# JW24A10L_revB.net
KiCad netlist of a schematic drawn in EAGLE
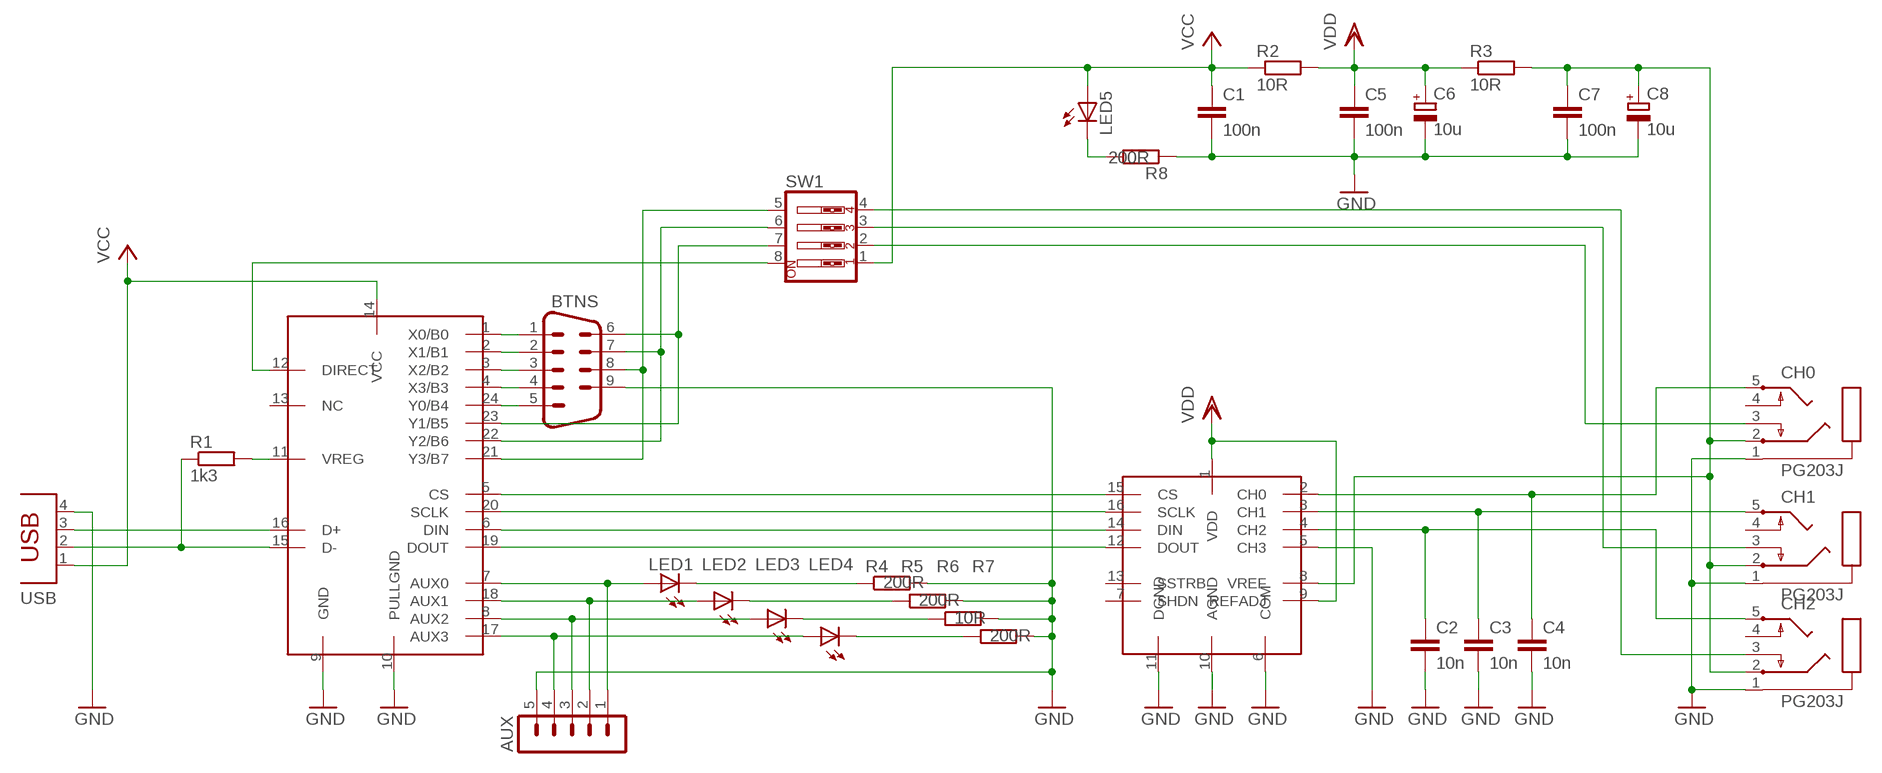
[diagram p0: schematic, sheet 1]

(export (version "E")
  (design (tool "Eeschema 10.0.6"))
  (components
    (comp (ref "AUX")
      (value "MA05-1")
      (footprint "eagle-import:MA05-1")
      (libsource (lib "eagle-import") (part "MA05-1"))
    )
    (comp (ref "BTNS")
      (value "M09H")
      (footprint "eagle-import:M09H")
      (libsource (lib "eagle-import") (part "M09H"))
    )
    (comp (ref "C1")
      (value "100n")
      (footprint "eagle-import:C025-025X050")
      (libsource (lib "eagle-import") (part "C-EU025-025X050"))
    )
    (comp (ref "C2")
      (value "10n")
      (footprint "eagle-import:C025-025X050")
      (libsource (lib "eagle-import") (part "C-EU025-025X050"))
    )
    (comp (ref "C3")
      (value "10n")
      (footprint "eagle-import:C025-025X050")
      (libsource (lib "eagle-import") (part "C-EU025-025X050"))
    )
    (comp (ref "C4")
      (value "10n")
      (footprint "eagle-import:C025-025X050")
      (libsource (lib "eagle-import") (part "C-EU025-025X050"))
    )
    (comp (ref "C5")
      (value "100n")
      (footprint "eagle-import:C025-025X050")
      (libsource (lib "eagle-import") (part "C-EU025-025X050"))
    )
    (comp (ref "C6")
      (value "10u")
      (footprint "eagle-import:E2-5")
      (libsource (lib "eagle-import") (part "CPOL-EUE2-5"))
    )
    (comp (ref "C7")
      (value "100n")
      (footprint "eagle-import:C025-025X050")
      (libsource (lib "eagle-import") (part "C-EU025-025X050"))
    )
    (comp (ref "C8")
      (value "10u")
      (footprint "eagle-import:E2-5")
      (libsource (lib "eagle-import") (part "CPOL-EUE2-5"))
    )
    (comp (ref "CH0")
      (value "PG203J")
      (footprint "eagle-import:PG203J")
      (libsource (lib "eagle-import") (part "PG203J"))
    )
    (comp (ref "CH1")
      (value "PG203J")
      (footprint "eagle-import:PG203J")
      (libsource (lib "eagle-import") (part "PG203J"))
    )
    (comp (ref "CH2")
      (value "PG203J")
      (footprint "eagle-import:PG203J")
      (libsource (lib "eagle-import") (part "PG203J"))
    )
    (comp (ref "LED1")
      (value "LED3MM")
      (footprint "eagle-import:LED3MM")
      (libsource (lib "eagle-import") (part "LED3MM"))
    )
    (comp (ref "LED2")
      (value "LED3MM")
      (footprint "eagle-import:LED3MM")
      (libsource (lib "eagle-import") (part "LED3MM"))
    )
    (comp (ref "LED3")
      (value "LED3MM")
      (footprint "eagle-import:LED3MM")
      (libsource (lib "eagle-import") (part "LED3MM"))
    )
    (comp (ref "LED4")
      (value "LED3MM")
      (footprint "eagle-import:LED3MM")
      (libsource (lib "eagle-import") (part "LED3MM"))
    )
    (comp (ref "LED5")
      (value "LED3MM")
      (footprint "eagle-import:LED3MM")
      (libsource (lib "eagle-import") (part "LED3MM"))
    )
    (comp (ref "R1")
      (value "1k3")
      (footprint "eagle-import:0204_7")
      (libsource (lib "eagle-import") (part "R-EU_0204/7"))
    )
    (comp (ref "R2")
      (value "10R")
      (footprint "eagle-import:0204_7")
      (libsource (lib "eagle-import") (part "R-EU_0204/7"))
    )
    (comp (ref "R3")
      (value "10R")
      (footprint "eagle-import:0204_7")
      (libsource (lib "eagle-import") (part "R-EU_0204/7"))
    )
    (comp (ref "R4")
      (value "200R")
      (footprint "eagle-import:0204_7")
      (libsource (lib "eagle-import") (part "R-EU_0204/7"))
    )
    (comp (ref "R5")
      (value "200R")
      (footprint "eagle-import:0204_7")
      (libsource (lib "eagle-import") (part "R-EU_0204/7"))
    )
    (comp (ref "R6")
      (value "10R")
      (footprint "eagle-import:0204_7")
      (libsource (lib "eagle-import") (part "R-EU_0204/7"))
    )
    (comp (ref "R7")
      (value "200R")
      (footprint "eagle-import:0204_7")
      (libsource (lib "eagle-import") (part "R-EU_0204/7"))
    )
    (comp (ref "R8")
      (value "200R")
      (footprint "eagle-import:0204_7")
      (libsource (lib "eagle-import") (part "R-EU_0204/7"))
    )
    (comp (ref "SW1")
      (value "SW_DIP-4")
      (footprint "eagle-import:EDG-04")
      (libsource (lib "eagle-import") (part "SW_DIP-4"))
    )
    (comp (ref "U$1")
      (value "MAX1249")
      (footprint "eagle-import:DIL16")
      (libsource (lib "eagle-import") (part "MAX1249"))
    )
    (comp (ref "U$2")
      (value "JW24A10L")
      (footprint "eagle-import:DIL24-3")
      (libsource (lib "eagle-import") (part "JW24A10L"))
    )
    (comp (ref "USB")
      (value "PN61729")
      (footprint "eagle-import:PN61729")
      (libsource (lib "eagle-import") (part "PN61729"))
    )
  )
  (nets
    (net (code "1") (name "GND") (class "Default")
      (node (ref "AUX") (pin "5") (pinfunction "5_5") (pintype "passive"))
      (node (ref "BTNS") (pin "9") (pinfunction "9_9") (pintype "passive"))
      (node (ref "C1") (pin "2") (pinfunction "2_2") (pintype "passive"))
      (node (ref "C2") (pin "2") (pinfunction "2_2") (pintype "passive"))
      (node (ref "C3") (pin "2") (pinfunction "2_2") (pintype "passive"))
      (node (ref "C4") (pin "2") (pinfunction "2_2") (pintype "passive"))
      (node (ref "C5") (pin "2") (pinfunction "2_2") (pintype "passive"))
      (node (ref "C6") (pin "-") (pinfunction "-_-") (pintype "passive"))
      (node (ref "C7") (pin "2") (pinfunction "2_2") (pintype "passive"))
      (node (ref "C8") (pin "-") (pinfunction "-_-") (pintype "passive"))
      (node (ref "CH0") (pin "1") (pinfunction "1_1") (pintype "passive"))
      (node (ref "CH1") (pin "1") (pinfunction "1_1") (pintype "passive"))
      (node (ref "CH2") (pin "1") (pinfunction "1_1") (pintype "passive"))
      (node (ref "R4") (pin "2") (pinfunction "2_2") (pintype "passive"))
      (node (ref "R5") (pin "2") (pinfunction "2_2") (pintype "passive"))
      (node (ref "R6") (pin "2") (pinfunction "2_2") (pintype "passive"))
      (node (ref "R7") (pin "2") (pinfunction "2_2") (pintype "passive"))
      (node (ref "R8") (pin "1") (pinfunction "1_1") (pintype "passive"))
      (node (ref "U$1") (pin "10") (pinfunction "AGND_10") (pintype "power_in"))
      (node (ref "U$1") (pin "11") (pinfunction "DGND_11") (pintype "power_in"))
      (node (ref "U$1") (pin "5") (pinfunction "CH3_5") (pintype "input"))
      (node (ref "U$1") (pin "6") (pinfunction "COM_6") (pintype "bidirectional"))
      (node (ref "U$2") (pin "10") (pinfunction "PULLGND_10") (pintype "power_in"))
      (node (ref "U$2") (pin "9") (pinfunction "GND_9") (pintype "power_in"))
      (node (ref "USB") (pin "4") (pinfunction "4_4") (pintype "passive"))
    )
    (net (code "2") (name "Net-(CH0-Pad3)") (class "Default")
      (node (ref "CH0") (pin "3") (pinfunction "3_3") (pintype "passive"))
      (node (ref "SW1") (pin "2") (pinfunction "2_2") (pintype "passive"))
    )
    (net (code "3") (name "Net-(CH1-Pad3)") (class "Default")
      (node (ref "CH1") (pin "3") (pinfunction "3_3") (pintype "passive"))
      (node (ref "SW1") (pin "3") (pinfunction "3_3") (pintype "passive"))
    )
    (net (code "4") (name "Net-(CH2-Pad3)") (class "Default")
      (node (ref "CH2") (pin "3") (pinfunction "3_3") (pintype "passive"))
      (node (ref "SW1") (pin "4") (pinfunction "4_4") (pintype "passive"))
    )
    (net (code "5") (name "Net-(LED1-C)") (class "Default")
      (node (ref "LED1") (pin "K") (pinfunction "C_K") (pintype "passive"))
      (node (ref "R4") (pin "1") (pinfunction "1_1") (pintype "passive"))
    )
    (net (code "6") (name "Net-(LED2-C)") (class "Default")
      (node (ref "LED2") (pin "K") (pinfunction "C_K") (pintype "passive"))
      (node (ref "R5") (pin "1") (pinfunction "1_1") (pintype "passive"))
    )
    (net (code "7") (name "Net-(LED3-C)") (class "Default")
      (node (ref "LED3") (pin "K") (pinfunction "C_K") (pintype "passive"))
      (node (ref "R6") (pin "1") (pinfunction "1_1") (pintype "passive"))
    )
    (net (code "8") (name "Net-(LED4-C)") (class "Default")
      (node (ref "LED4") (pin "K") (pinfunction "C_K") (pintype "passive"))
      (node (ref "R7") (pin "1") (pinfunction "1_1") (pintype "passive"))
    )
    (net (code "9") (name "Net-(LED5-C)") (class "Default")
      (node (ref "LED5") (pin "K") (pinfunction "C_K") (pintype "passive"))
      (node (ref "R8") (pin "2") (pinfunction "2_2") (pintype "passive"))
    )
    (net (code "10") (name "Net-(U$1-CH0)") (class "Default")
      (node (ref "C4") (pin "1") (pinfunction "1_1") (pintype "passive"))
      (node (ref "CH0") (pin "5") (pinfunction "5_5") (pintype "passive"))
      (node (ref "U$1") (pin "2") (pinfunction "CH0_2") (pintype "input"))
    )
    (net (code "11") (name "Net-(U$1-CH1)") (class "Default")
      (node (ref "C3") (pin "1") (pinfunction "1_1") (pintype "passive"))
      (node (ref "CH1") (pin "5") (pinfunction "5_5") (pintype "passive"))
      (node (ref "U$1") (pin "3") (pinfunction "CH1_3") (pintype "input"))
    )
    (net (code "12") (name "Net-(U$1-CH2)") (class "Default")
      (node (ref "C2") (pin "1") (pinfunction "1_1") (pintype "passive"))
      (node (ref "CH2") (pin "5") (pinfunction "5_5") (pintype "passive"))
      (node (ref "U$1") (pin "4") (pinfunction "CH2_4") (pintype "input"))
    )
    (net (code "13") (name "Net-(U$1-CS)") (class "Default")
      (node (ref "U$1") (pin "15") (pinfunction "CS_15") (pintype "bidirectional"))
      (node (ref "U$2") (pin "5") (pinfunction "CS_5") (pintype "bidirectional"))
    )
    (net (code "14") (name "Net-(U$1-DIN)") (class "Default")
      (node (ref "U$1") (pin "14") (pinfunction "DIN_14") (pintype "bidirectional"))
      (node (ref "U$2") (pin "6") (pinfunction "DIN_6") (pintype "bidirectional"))
    )
    (net (code "15") (name "Net-(U$1-DOUT)") (class "Default")
      (node (ref "U$1") (pin "12") (pinfunction "DOUT_12") (pintype "bidirectional"))
      (node (ref "U$2") (pin "19") (pinfunction "DOUT_19") (pintype "bidirectional"))
    )
    (net (code "16") (name "Net-(U$1-SCLK)") (class "Default")
      (node (ref "U$1") (pin "16") (pinfunction "SCLK_16") (pintype "bidirectional"))
      (node (ref "U$2") (pin "20") (pinfunction "SCLK_20") (pintype "bidirectional"))
    )
    (net (code "17") (name "Net-(U$1-VREF)") (class "Default")
      (node (ref "C7") (pin "1") (pinfunction "1_1") (pintype "passive"))
      (node (ref "C8") (pin "+") (pinfunction "+_+") (pintype "passive"))
      (node (ref "CH0") (pin "2") (pinfunction "2_2") (pintype "passive"))
      (node (ref "CH1") (pin "2") (pinfunction "2_2") (pintype "passive"))
      (node (ref "CH2") (pin "2") (pinfunction "2_2") (pintype "passive"))
      (node (ref "R3") (pin "2") (pinfunction "2_2") (pintype "passive"))
      (node (ref "U$1") (pin "8") (pinfunction "VREF_8") (pintype "bidirectional"))
    )
    (net (code "18") (name "Net-(U$2-AUX0)") (class "Default")
      (node (ref "AUX") (pin "1") (pinfunction "1_1") (pintype "passive"))
      (node (ref "LED1") (pin "A") (pinfunction "A_A") (pintype "passive"))
      (node (ref "U$2") (pin "7") (pinfunction "AUX0_7") (pintype "power_in"))
    )
    (net (code "19") (name "Net-(U$2-AUX1)") (class "Default")
      (node (ref "AUX") (pin "2") (pinfunction "2_2") (pintype "passive"))
      (node (ref "LED2") (pin "A") (pinfunction "A_A") (pintype "passive"))
      (node (ref "U$2") (pin "18") (pinfunction "AUX1_18") (pintype "power_in"))
    )
    (net (code "20") (name "Net-(U$2-AUX2)") (class "Default")
      (node (ref "AUX") (pin "3") (pinfunction "3_3") (pintype "passive"))
      (node (ref "LED3") (pin "A") (pinfunction "A_A") (pintype "passive"))
      (node (ref "U$2") (pin "8") (pinfunction "AUX2_8") (pintype "power_in"))
    )
    (net (code "21") (name "Net-(U$2-AUX3)") (class "Default")
      (node (ref "AUX") (pin "4") (pinfunction "4_4") (pintype "passive"))
      (node (ref "LED4") (pin "A") (pinfunction "A_A") (pintype "passive"))
      (node (ref "U$2") (pin "17") (pinfunction "AUX3_17") (pintype "power_in"))
    )
    (net (code "22") (name "Net-(U$2-D+)") (class "Default")
      (node (ref "U$2") (pin "16") (pinfunction "D+_16") (pintype "bidirectional"))
      (node (ref "USB") (pin "3") (pinfunction "3_3") (pintype "passive"))
    )
    (net (code "23") (name "Net-(U$2-D-)") (class "Default")
      (node (ref "R1") (pin "1") (pinfunction "1_1") (pintype "passive"))
      (node (ref "U$2") (pin "15") (pinfunction "D-_15") (pintype "bidirectional"))
      (node (ref "USB") (pin "2") (pinfunction "2_2") (pintype "passive"))
    )
    (net (code "24") (name "Net-(U$2-DIRECT)") (class "Default")
      (node (ref "SW1") (pin "8") (pinfunction "8_8") (pintype "passive"))
      (node (ref "U$2") (pin "12") (pinfunction "DIRECT_12") (pintype "bidirectional"))
    )
    (net (code "25") (name "Net-(U$2-VREG)") (class "Default")
      (node (ref "R1") (pin "2") (pinfunction "2_2") (pintype "passive"))
      (node (ref "U$2") (pin "11") (pinfunction "VREG_11") (pintype "bidirectional"))
    )
    (net (code "26") (name "Net-(U$2-X0{slash}B0)") (class "Default")
      (node (ref "BTNS") (pin "1") (pinfunction "1_1") (pintype "passive"))
      (node (ref "U$2") (pin "1") (pinfunction "X0/B0_1") (pintype "bidirectional"))
    )
    (net (code "27") (name "Net-(U$2-X1{slash}B1)") (class "Default")
      (node (ref "BTNS") (pin "2") (pinfunction "2_2") (pintype "passive"))
      (node (ref "U$2") (pin "2") (pinfunction "X1/B1_2") (pintype "bidirectional"))
    )
    (net (code "28") (name "Net-(U$2-X2{slash}B2)") (class "Default")
      (node (ref "BTNS") (pin "3") (pinfunction "3_3") (pintype "passive"))
      (node (ref "U$2") (pin "3") (pinfunction "X2/B2_3") (pintype "bidirectional"))
    )
    (net (code "29") (name "Net-(U$2-X3{slash}B3)") (class "Default")
      (node (ref "BTNS") (pin "4") (pinfunction "4_4") (pintype "passive"))
      (node (ref "U$2") (pin "4") (pinfunction "X3/B3_4") (pintype "bidirectional"))
    )
    (net (code "30") (name "Net-(U$2-Y0{slash}B4)") (class "Default")
      (node (ref "BTNS") (pin "5") (pinfunction "5_5") (pintype "passive"))
      (node (ref "U$2") (pin "24") (pinfunction "Y0/B4_24") (pintype "bidirectional"))
    )
    (net (code "31") (name "Net-(U$2-Y1{slash}B5)") (class "Default")
      (node (ref "BTNS") (pin "6") (pinfunction "6_6") (pintype "passive"))
      (node (ref "SW1") (pin "7") (pinfunction "7_7") (pintype "passive"))
      (node (ref "U$2") (pin "23") (pinfunction "Y1/B5_23") (pintype "bidirectional"))
    )
    (net (code "32") (name "Net-(U$2-Y2{slash}B6)") (class "Default")
      (node (ref "BTNS") (pin "7") (pinfunction "7_7") (pintype "passive"))
      (node (ref "SW1") (pin "6") (pinfunction "6_6") (pintype "passive"))
      (node (ref "U$2") (pin "22") (pinfunction "Y2/B6_22") (pintype "bidirectional"))
    )
    (net (code "33") (name "Net-(U$2-Y3{slash}B7)") (class "Default")
      (node (ref "BTNS") (pin "8") (pinfunction "8_8") (pintype "passive"))
      (node (ref "SW1") (pin "5") (pinfunction "5_5") (pintype "passive"))
      (node (ref "U$2") (pin "21") (pinfunction "Y3/B7_21") (pintype "bidirectional"))
    )
    (net (code "34") (name "VCC") (class "Default")
      (node (ref "C1") (pin "1") (pinfunction "1_1") (pintype "passive"))
      (node (ref "LED5") (pin "A") (pinfunction "A_A") (pintype "passive"))
      (node (ref "R2") (pin "1") (pinfunction "1_1") (pintype "passive"))
      (node (ref "SW1") (pin "1") (pinfunction "1_1") (pintype "passive"))
      (node (ref "U$2") (pin "14") (pinfunction "VCC_14") (pintype "power_in"))
      (node (ref "USB") (pin "1") (pinfunction "1_1") (pintype "passive"))
    )
    (net (code "35") (name "VDD") (class "Default")
      (node (ref "C5") (pin "1") (pinfunction "1_1") (pintype "passive"))
      (node (ref "C6") (pin "+") (pinfunction "+_+") (pintype "passive"))
      (node (ref "R2") (pin "2") (pinfunction "2_2") (pintype "passive"))
      (node (ref "R3") (pin "1") (pinfunction "1_1") (pintype "passive"))
      (node (ref "U$1") (pin "1") (pinfunction "VDD_1") (pintype "power_in"))
      (node (ref "U$1") (pin "9") (pinfunction "REFADJ_9") (pintype "bidirectional"))
    )
    (net (code "36") (name "unconnected-(CH0-Pad4)") (class "Default")
      (node (ref "CH0") (pin "4") (pinfunction "4_4") (pintype "passive"))
    )
    (net (code "37") (name "unconnected-(CH1-Pad4)") (class "Default")
      (node (ref "CH1") (pin "4") (pinfunction "4_4") (pintype "passive"))
    )
    (net (code "38") (name "unconnected-(CH2-Pad4)") (class "Default")
      (node (ref "CH2") (pin "4") (pinfunction "4_4") (pintype "passive"))
    )
    (net (code "39") (name "unconnected-(U$1-SHDN-Pad7)") (class "Default")
      (node (ref "U$1") (pin "7") (pinfunction "SHDN_7") (pintype "bidirectional"))
    )
    (net (code "40") (name "unconnected-(U$1-SSTRB-Pad13)") (class "Default")
      (node (ref "U$1") (pin "13") (pinfunction "SSTRB_13") (pintype "bidirectional"))
    )
    (net (code "41") (name "unconnected-(U$2-NC-Pad13)") (class "Default")
      (node (ref "U$2") (pin "13") (pinfunction "NC_13") (pintype "bidirectional"))
    )
  )
)
